# 1_3_2_Power_board_BAT3_BAT4.net
KiCad netlist of a schematic drawn in Altium Designer
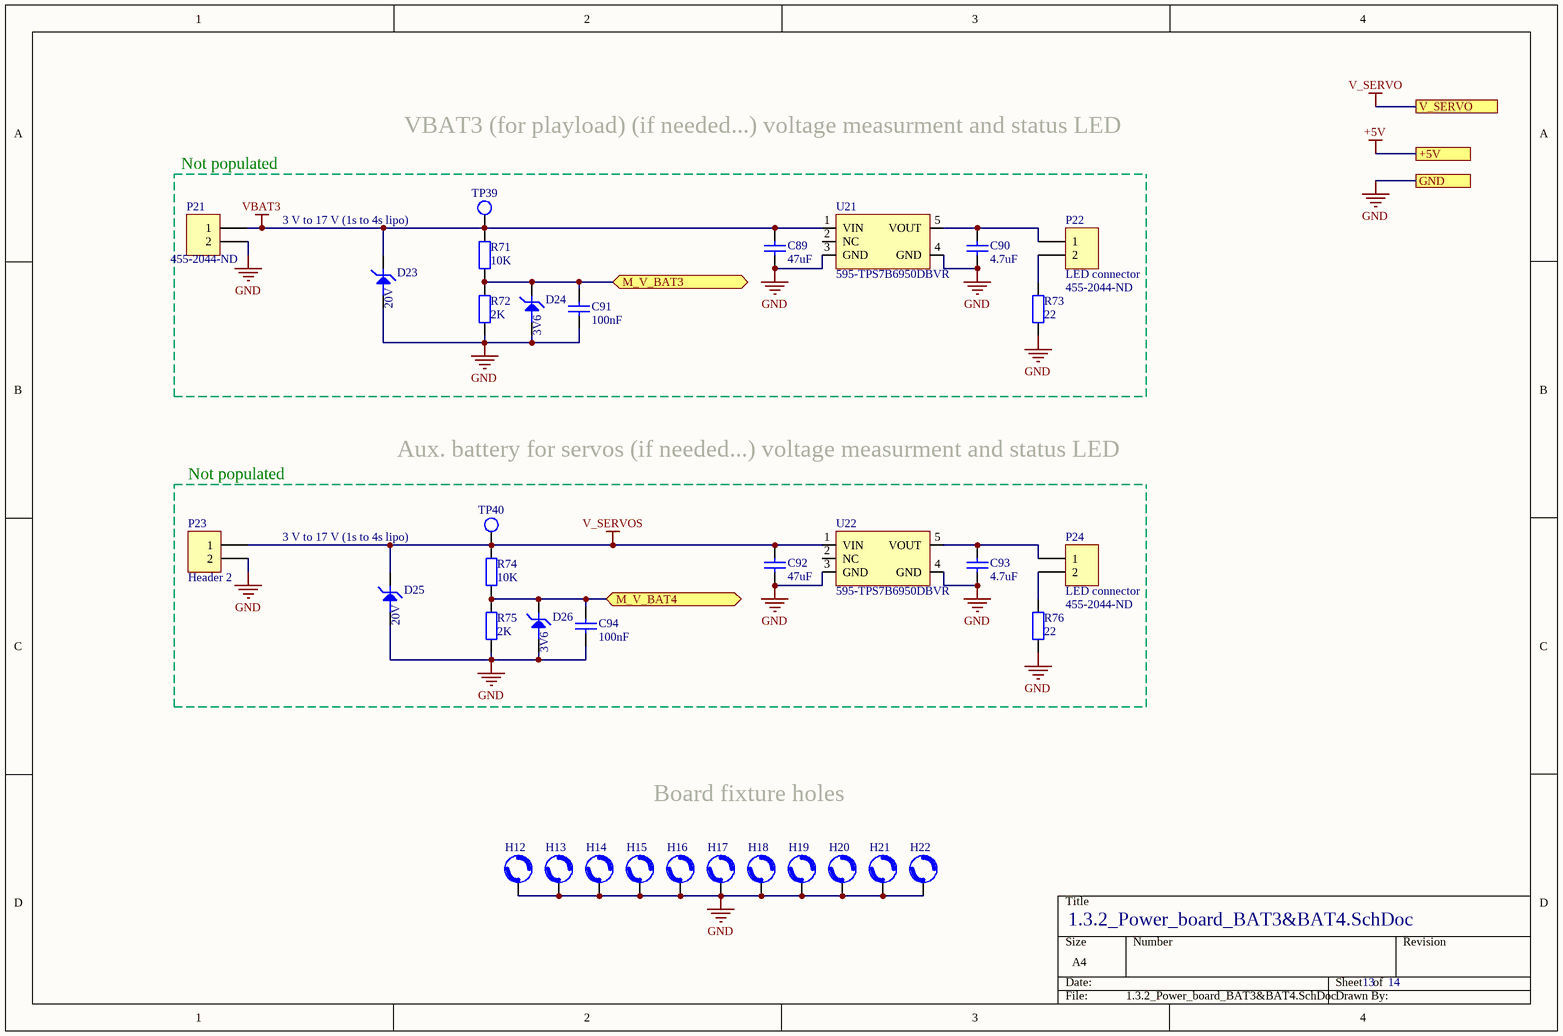
[diagram p0: 1.3.2_Power_board_BAT3&BAT4.SchDoc]

(export (version "E")
  (design (tool "Eeschema 10.0.6"))
  (components
    (comp (ref "C89")
      (value "47uF")
      (footprint "CAP1206W")
      (description "Capacitor")
      (libsource (lib "Rocket_library") (part "C_47uF_25v_1206"))
    )
    (comp (ref "C90")
      (value "4.7uF")
      (footprint "CAP0805W")
      (description "Capacitor")
      (libsource (lib "Rocket_library") (part "C_4.7uF_16v"))
    )
    (comp (ref "C91")
      (value "100nF")
      (footprint "CAP0603R")
      (description "Capacitor")
      (libsource (lib "Rocket_library") (part "C_100nF"))
    )
    (comp (ref "C92")
      (value "47uF")
      (footprint "CAP1206W")
      (description "Capacitor")
      (libsource (lib "Rocket_library") (part "C_47uF_25v_1206"))
    )
    (comp (ref "C93")
      (value "4.7uF")
      (footprint "CAP0805W")
      (description "Capacitor")
      (libsource (lib "Rocket_library") (part "C_4.7uF_16v"))
    )
    (comp (ref "C94")
      (value "100nF")
      (footprint "CAP0603R")
      (description "Capacitor")
      (libsource (lib "Rocket_library") (part "C_100nF"))
    )
    (comp (ref "D23")
      (value "20V")
      (footprint "DO-214AA")
      (description "Zener Diodes 5W 20V")
      (libsource (lib "Rocket_library") (part "DZ_20V"))
    )
    (comp (ref "D24")
      (value "3V6")
      (footprint "SOT23")
      (description "Zener Diodes 3.6V 225mW")
      (libsource (lib "Rocket_library") (part "DZ_3V6_MMBZ522"))
    )
    (comp (ref "D25")
      (value "20V")
      (footprint "DO-214AA")
      (description "Zener Diodes 5W 20V")
      (libsource (lib "Rocket_library") (part "DZ_20V"))
    )
    (comp (ref "D26")
      (value "3V6")
      (footprint "SOT23")
      (description "Zener Diodes 3.6V 225mW")
      (libsource (lib "Rocket_library") (part "DZ_3V6_MMBZ522"))
    )
    (comp (ref "H12")
      (value "Hole_3.2mm")
      (footprint "HOLE_3.2mm")
      (libsource (lib "Rocket_library") (part "Hole_3.2mm"))
    )
    (comp (ref "H13")
      (value "Hole_3.2mm")
      (footprint "HOLE_3.2mm")
      (libsource (lib "Rocket_library") (part "Hole_3.2mm"))
    )
    (comp (ref "H14")
      (value "Hole_3.2mm")
      (footprint "HOLE_3.2mm")
      (libsource (lib "Rocket_library") (part "Hole_3.2mm"))
    )
    (comp (ref "H15")
      (value "Hole_3.2mm")
      (footprint "HOLE_3.2mm")
      (libsource (lib "Rocket_library") (part "Hole_3.2mm"))
    )
    (comp (ref "H16")
      (value "Hole_3.2mm")
      (footprint "HOLE_3.2mm")
      (libsource (lib "Rocket_library") (part "Hole_3.2mm"))
    )
    (comp (ref "H17")
      (value "Hole_3.2mm")
      (footprint "HOLE_3.2mm")
      (libsource (lib "Rocket_library") (part "Hole_3.2mm"))
    )
    (comp (ref "H18")
      (value "Hole_3.2mm")
      (footprint "HOLE_3.2mm")
      (libsource (lib "Rocket_library") (part "Hole_3.2mm"))
    )
    (comp (ref "H19")
      (value "Hole_3.2mm")
      (footprint "HOLE_3.2mm")
      (libsource (lib "Rocket_library") (part "Hole_3.2mm"))
    )
    (comp (ref "H20")
      (value "Hole_3.2mm")
      (footprint "HOLE_3.2mm")
      (libsource (lib "Rocket_library") (part "Hole_3.2mm"))
    )
    (comp (ref "H21")
      (value "Hole_3.2mm")
      (footprint "HOLE_3.2mm")
      (libsource (lib "Rocket_library") (part "Hole_3.2mm"))
    )
    (comp (ref "H22")
      (value "Hole_3.2mm")
      (footprint "HOLE_3.2mm")
      (libsource (lib "Rocket_library") (part "Hole_3.2mm"))
    )
    (comp (ref "P21")
      (value "~")
      (footprint "CON_JST_XA_ S02B-XASS-1")
      (description "Header 2p JST XA 3A right angle")
      (fields (field (name "SUPPLIER PART NUMBER 1") "455-2044-ND"))
      (libsource (lib "Rocket_library") (part "Header 2p JST XA 3A right angle"))
    )
    (comp (ref "P22")
      (value "LED connector")
      (footprint "CON_JST_XA_ S02B-XASS-1")
      (description "Header 2p JST XA 3A right angle")
      (fields (field (name "SUPPLIER PART NUMBER 1") "455-2044-ND"))
      (libsource (lib "") (part "Header 2p JST XA 3A right angle_1"))
    )
    (comp (ref "P23")
      (value "Header 2")
      (footprint "Con Prov 2P Power")
      (description "Juste pour tester!!!")
      (libsource (lib "Rocket_library") (part "Header 2"))
    )
    (comp (ref "P24")
      (value "LED connector")
      (footprint "CON_JST_XA_ S02B-XASS-1")
      (description "Header 2p JST XA 3A right angle")
      (fields (field (name "SUPPLIER PART NUMBER 1") "455-2044-ND"))
      (libsource (lib "") (part "Header 2p JST XA 3A right angle_1"))
    )
    (comp (ref "R71")
      (value "10K")
      (footprint "0603")
      (description "0.1W 10K")
      (libsource (lib "Rocket_library") (part "R_0603_01W_10K"))
    )
    (comp (ref "R72")
      (value "2K")
      (footprint "0603")
      (description "0.1W 2K")
      (libsource (lib "Rocket_library") (part "R_0603_01W_2K"))
    )
    (comp (ref "R73")
      (value "22")
      (footprint "0603")
      (description "0.25W 22Ohm")
      (libsource (lib "Rocket_library") (part "R_0603_025W_22Ohm"))
    )
    (comp (ref "R74")
      (value "10K")
      (footprint "0603")
      (description "0.1W 10K")
      (libsource (lib "Rocket_library") (part "R_0603_01W_10K"))
    )
    (comp (ref "R75")
      (value "2K")
      (footprint "0603")
      (description "0.1W 2K")
      (libsource (lib "Rocket_library") (part "R_0603_01W_2K"))
    )
    (comp (ref "R76")
      (value "22")
      (footprint "0603")
      (description "0.25W 22Ohm")
      (libsource (lib "Rocket_library") (part "R_0603_025W_22Ohm"))
    )
    (comp (ref "TP39")
      (value "Test point")
      (footprint "TP")
      (libsource (lib "Rocket_library") (part "Test point"))
    )
    (comp (ref "TP40")
      (value "Test point")
      (footprint "TP")
      (libsource (lib "Rocket_library") (part "Test point"))
    )
    (comp (ref "U21")
      (value "TPS7B6950D")
      (footprint "SOT-23-5")
      (description "LDO 5V 150mA")
      (fields (field (name "SUPPLIER PART NUMBER 1") "595-TPS7B6950DBVR"))
      (libsource (lib "Rocket_library") (part "TPS7B6950D"))
    )
    (comp (ref "U22")
      (value "TPS7B6950D")
      (footprint "SOT-23-5")
      (description "LDO 5V 150mA")
      (fields (field (name "SUPPLIER PART NUMBER 1") "595-TPS7B6950DBVR"))
      (libsource (lib "Rocket_library") (part "TPS7B6950D"))
    )
  )
  (nets
    (net (code "2") (name "/M_V_BAT3") (class "Default")
      (node (ref "C91") (pin "2") (pinfunction "2_2") (pintype "passive"))
      (node (ref "D24") (pin "3") (pintype "passive"))
      (node (ref "R71") (pin "1") (pinfunction "1_1") (pintype "passive"))
      (node (ref "R72") (pin "2") (pinfunction "2_2") (pintype "passive"))
    )
    (net (code "3") (name "/M_V_BAT4") (class "Default")
      (node (ref "C94") (pin "2") (pinfunction "2_2") (pintype "passive"))
      (node (ref "D26") (pin "3") (pintype "passive"))
      (node (ref "R74") (pin "1") (pinfunction "1_1") (pintype "passive"))
      (node (ref "R75") (pin "2") (pinfunction "2_2") (pintype "passive"))
    )
    (net (code "4") (name "GND") (class "Default")
      (node (ref "C89") (pin "1") (pinfunction "1_1") (pintype "passive"))
      (node (ref "C90") (pin "1") (pinfunction "1_1") (pintype "passive"))
      (node (ref "C91") (pin "1") (pinfunction "1_1") (pintype "passive"))
      (node (ref "C92") (pin "1") (pinfunction "1_1") (pintype "passive"))
      (node (ref "C93") (pin "1") (pinfunction "1_1") (pintype "passive"))
      (node (ref "C94") (pin "1") (pinfunction "1_1") (pintype "passive"))
      (node (ref "D23") (pin "A") (pintype "passive"))
      (node (ref "D24") (pin "1") (pintype "passive"))
      (node (ref "D25") (pin "A") (pintype "passive"))
      (node (ref "D26") (pin "1") (pintype "passive"))
      (node (ref "H12") (pin "0") (pinfunction "0_0") (pintype "passive"))
      (node (ref "H13") (pin "0") (pinfunction "0_0") (pintype "passive"))
      (node (ref "H14") (pin "0") (pinfunction "0_0") (pintype "passive"))
      (node (ref "H15") (pin "0") (pinfunction "0_0") (pintype "passive"))
      (node (ref "H16") (pin "0") (pinfunction "0_0") (pintype "passive"))
      (node (ref "H17") (pin "0") (pinfunction "0_0") (pintype "passive"))
      (node (ref "H18") (pin "0") (pinfunction "0_0") (pintype "passive"))
      (node (ref "H19") (pin "0") (pinfunction "0_0") (pintype "passive"))
      (node (ref "H20") (pin "0") (pinfunction "0_0") (pintype "passive"))
      (node (ref "H21") (pin "0") (pinfunction "0_0") (pintype "passive"))
      (node (ref "H22") (pin "0") (pinfunction "0_0") (pintype "passive"))
      (node (ref "P21") (pin "2") (pinfunction "2_2") (pintype "passive"))
      (node (ref "P23") (pin "2") (pinfunction "2_2") (pintype "passive"))
      (node (ref "R72") (pin "1") (pinfunction "1_1") (pintype "passive"))
      (node (ref "R73") (pin "1") (pinfunction "1_1") (pintype "passive"))
      (node (ref "R75") (pin "1") (pinfunction "1_1") (pintype "passive"))
      (node (ref "R76") (pin "1") (pinfunction "1_1") (pintype "passive"))
      (node (ref "U21") (pin "3") (pinfunction "GND_3") (pintype "passive"))
      (node (ref "U21") (pin "4") (pinfunction "GND_4") (pintype "passive"))
      (node (ref "U22") (pin "3") (pinfunction "GND_3") (pintype "passive"))
      (node (ref "U22") (pin "4") (pinfunction "GND_4") (pintype "passive"))
    )
    (net (code "5") (name "Net-(P22-Pad2)") (class "Default")
      (node (ref "P22") (pin "2") (pinfunction "2_2") (pintype "passive"))
      (node (ref "R73") (pin "2") (pinfunction "2_2") (pintype "passive"))
    )
    (net (code "6") (name "Net-(P24-Pad2)") (class "Default")
      (node (ref "P24") (pin "2") (pinfunction "2_2") (pintype "passive"))
      (node (ref "R76") (pin "2") (pinfunction "2_2") (pintype "passive"))
    )
    (net (code "7") (name "Net-(U21-VOUT)") (class "Default")
      (node (ref "C90") (pin "2") (pinfunction "2_2") (pintype "passive"))
      (node (ref "P22") (pin "1") (pinfunction "1_1") (pintype "passive"))
      (node (ref "U21") (pin "5") (pinfunction "VOUT_5") (pintype "passive"))
    )
    (net (code "8") (name "Net-(U22-VOUT)") (class "Default")
      (node (ref "C93") (pin "2") (pinfunction "2_2") (pintype "passive"))
      (node (ref "P24") (pin "1") (pinfunction "1_1") (pintype "passive"))
      (node (ref "U22") (pin "5") (pinfunction "VOUT_5") (pintype "passive"))
    )
    (net (code "9") (name "VBAT3") (class "Default")
      (node (ref "C89") (pin "2") (pinfunction "2_2") (pintype "passive"))
      (node (ref "D23") (pin "C") (pintype "passive"))
      (node (ref "P21") (pin "1") (pinfunction "1_1") (pintype "passive"))
      (node (ref "R71") (pin "2") (pinfunction "2_2") (pintype "passive"))
      (node (ref "TP39") (pin "1") (pinfunction "1_1") (pintype "passive"))
      (node (ref "U21") (pin "1") (pinfunction "VIN_1") (pintype "passive"))
    )
    (net (code "11") (name "V_SERVOS") (class "Default")
      (node (ref "C92") (pin "2") (pinfunction "2_2") (pintype "passive"))
      (node (ref "D25") (pin "C") (pintype "passive"))
      (node (ref "P23") (pin "1") (pinfunction "1_1") (pintype "passive"))
      (node (ref "R74") (pin "2") (pinfunction "2_2") (pintype "passive"))
      (node (ref "TP40") (pin "1") (pinfunction "1_1") (pintype "passive"))
      (node (ref "U22") (pin "1") (pinfunction "VIN_1") (pintype "passive"))
    )
    (net (code "12") (name "unconnected-(U21-NC-Pad2)") (class "Default")
      (node (ref "U21") (pin "2") (pinfunction "NC_2") (pintype "passive"))
    )
    (net (code "13") (name "unconnected-(U22-NC-Pad2)") (class "Default")
      (node (ref "U22") (pin "2") (pinfunction "NC_2") (pintype "passive"))
    )
  )
)
